# LedMatrixController.net
KiCad netlist of a schematic drawn in EAGLE
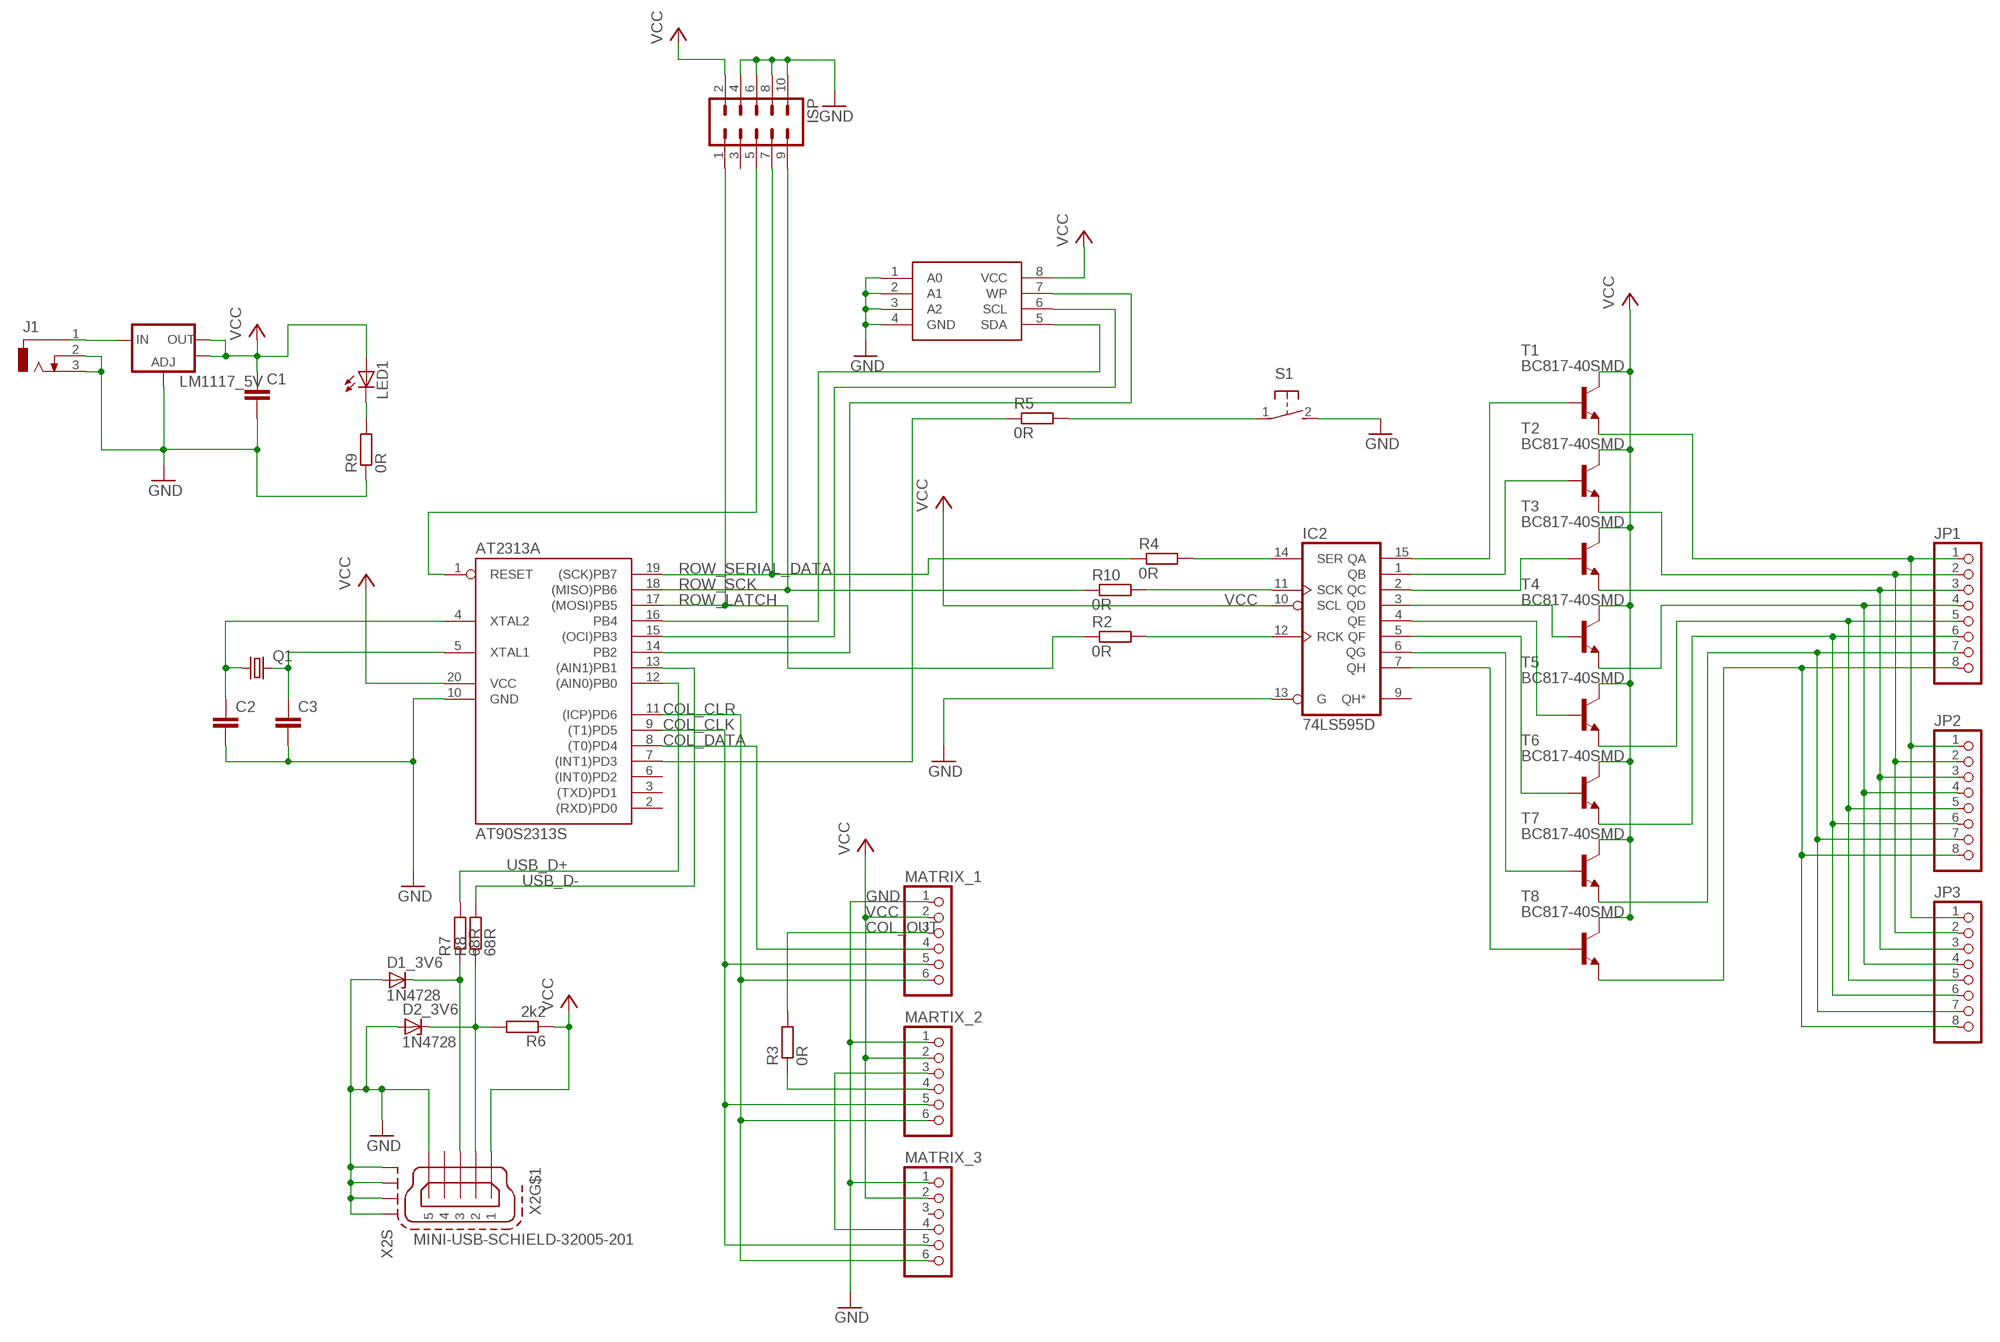
[diagram p0: schematic, sheet 1]

(export (version "E")
  (design (tool "Eeschema 10.0.6"))
  (components
    (comp (ref "AT2313A")
      (value "AT90S2313S")
      (footprint "eagle-import:SO20L")
      (libsource (lib "eagle-import") (part "AT90S2313S"))
    )
    (comp (ref "C1")
      (value "C-EU025-025X050")
      (footprint "eagle-import:C025-025X050")
      (libsource (lib "eagle-import") (part "C-EU025-025X050"))
    )
    (comp (ref "C2")
      (value "C-EUC1206")
      (footprint "eagle-import:C1206")
      (libsource (lib "eagle-import") (part "C-EUC1206"))
    )
    (comp (ref "C3")
      (value "C-EUC1206")
      (footprint "eagle-import:C1206")
      (libsource (lib "eagle-import") (part "C-EUC1206"))
    )
    (comp (ref "D1_3V6")
      (value "1N4728")
      (footprint "eagle-import:DO41Z10")
      (libsource (lib "eagle-import") (part "1N4728"))
    )
    (comp (ref "D2_3V6")
      (value "1N4728")
      (footprint "eagle-import:DO41Z10")
      (libsource (lib "eagle-import") (part "1N4728"))
    )
    (comp (ref "EEPROM")
      (value "AT24C08")
      (footprint "eagle-import:SO08")
      (libsource (lib "eagle-import") (part "AT24C08"))
    )
    (comp (ref "IC2")
      (value "74LS595D")
      (footprint "eagle-import:SO16")
      (libsource (lib "eagle-import") (part "74595DLS"))
    )
    (comp (ref "ISP")
      (value "ML10")
      (footprint "eagle-import:ML10")
      (libsource (lib "eagle-import") (part "ML10"))
    )
    (comp (ref "J1")
      (value "DCJ0303")
      (footprint "eagle-import:DCJ0303")
      (libsource (lib "eagle-import") (part "DCJ0303"))
    )
    (comp (ref "JP1")
      (value "PINHD-1X8")
      (footprint "eagle-import:1X08")
      (libsource (lib "eagle-import") (part "PINHD-1X8"))
    )
    (comp (ref "JP2")
      (value "PINHD-1X8")
      (footprint "eagle-import:1X08")
      (libsource (lib "eagle-import") (part "PINHD-1X8"))
    )
    (comp (ref "JP3")
      (value "PINHD-1X8")
      (footprint "eagle-import:1X08")
      (libsource (lib "eagle-import") (part "PINHD-1X8"))
    )
    (comp (ref "LED1")
      (value "LEDCHIPLED_1206")
      (footprint "eagle-import:CHIPLED_1206")
      (libsource (lib "eagle-import") (part "LEDCHIPLED_1206"))
    )
    (comp (ref "LM1117_5V")
      (value "V_REG_LM1117SOT223")
      (footprint "eagle-import:SOT223")
      (libsource (lib "eagle-import") (part "V_REG_LM1117SOT223"))
    )
    (comp (ref "MARTIX_2")
      (value "PINHD-1X6")
      (footprint "eagle-import:1X06")
      (libsource (lib "eagle-import") (part "PINHD-1X6"))
    )
    (comp (ref "MATRIX_1")
      (value "PINHD-1X6")
      (footprint "eagle-import:1X06")
      (libsource (lib "eagle-import") (part "PINHD-1X6"))
    )
    (comp (ref "MATRIX_3")
      (value "PINHD-1X6")
      (footprint "eagle-import:1X06")
      (libsource (lib "eagle-import") (part "PINHD-1X6"))
    )
    (comp (ref "Q1")
      (value "CRYSTALHC49UP")
      (footprint "eagle-import:HC49UP")
      (libsource (lib "eagle-import") (part "CRYSTALHC49UP"))
    )
    (comp (ref "R2")
      (value "0R")
      (footprint "eagle-import:R1206")
      (libsource (lib "eagle-import") (part "R-EU_R1206"))
    )
    (comp (ref "R3")
      (value "0R")
      (footprint "eagle-import:R1206")
      (libsource (lib "eagle-import") (part "R-EU_R1206"))
    )
    (comp (ref "R4")
      (value "0R")
      (footprint "eagle-import:R1206")
      (libsource (lib "eagle-import") (part "R-EU_R1206"))
    )
    (comp (ref "R5")
      (value "0R")
      (footprint "eagle-import:R1206")
      (libsource (lib "eagle-import") (part "R-EU_R1206"))
    )
    (comp (ref "R6")
      (value "2k2")
      (footprint "eagle-import:R1206")
      (libsource (lib "eagle-import") (part "R-EU_R1206"))
    )
    (comp (ref "R7")
      (value "68R")
      (footprint "eagle-import:R1206")
      (libsource (lib "eagle-import") (part "R-EU_R1206"))
    )
    (comp (ref "R8")
      (value "68R")
      (footprint "eagle-import:R1206")
      (libsource (lib "eagle-import") (part "R-EU_R1206"))
    )
    (comp (ref "R9")
      (value "0R")
      (footprint "eagle-import:R1206")
      (libsource (lib "eagle-import") (part "R-EU_R1206"))
    )
    (comp (ref "R10")
      (value "0R")
      (footprint "eagle-import:R1206")
      (libsource (lib "eagle-import") (part "R-EU_R1206"))
    )
    (comp (ref "S1")
      (value "31-XX")
      (footprint "eagle-import:B3F-31XX")
      (fields (field (name "MPN") "B3F-3100"))
      (libsource (lib "eagle-import") (part "31-XX"))
    )
    (comp (ref "T1")
      (value "BC817-40SMD")
      (footprint "eagle-import:SOT23-BEC")
      (libsource (lib "eagle-import") (part "BC817SMD-40"))
    )
    (comp (ref "T2")
      (value "BC817-40SMD")
      (footprint "eagle-import:SOT23-BEC")
      (libsource (lib "eagle-import") (part "BC817SMD-40"))
    )
    (comp (ref "T3")
      (value "BC817-40SMD")
      (footprint "eagle-import:SOT23-BEC")
      (libsource (lib "eagle-import") (part "BC817SMD-40"))
    )
    (comp (ref "T4")
      (value "BC817-40SMD")
      (footprint "eagle-import:SOT23-BEC")
      (libsource (lib "eagle-import") (part "BC817SMD-40"))
    )
    (comp (ref "T5")
      (value "BC817-40SMD")
      (footprint "eagle-import:SOT23-BEC")
      (libsource (lib "eagle-import") (part "BC817SMD-40"))
    )
    (comp (ref "T6")
      (value "BC817-40SMD")
      (footprint "eagle-import:SOT23-BEC")
      (libsource (lib "eagle-import") (part "BC817SMD-40"))
    )
    (comp (ref "T7")
      (value "BC817-40SMD")
      (footprint "eagle-import:SOT23-BEC")
      (libsource (lib "eagle-import") (part "BC817SMD-40"))
    )
    (comp (ref "T8")
      (value "BC817-40SMD")
      (footprint "eagle-import:SOT23-BEC")
      (libsource (lib "eagle-import") (part "BC817SMD-40"))
    )
    (comp (ref "X2")
      (value "MINI-USB-SCHIELD-32005-201")
      (footprint "eagle-import:32005-201")
      (libsource (lib "eagle-import") (part "MINI-USB-SCHIELD-32005-201"))
    )
  )
  (nets
    (net (code "1") (name "/COL_CLK") (class "Default")
      (node (ref "AT2313A") (pin "9") (pinfunction "(T1)PD5_9") (pintype "bidirectional"))
      (node (ref "MARTIX_2") (pin "5") (pinfunction "5_5") (pintype "passive"))
      (node (ref "MATRIX_1") (pin "5") (pinfunction "5_5") (pintype "passive"))
      (node (ref "MATRIX_3") (pin "5") (pinfunction "5_5") (pintype "passive"))
    )
    (net (code "2") (name "/COL_CLR") (class "Default")
      (node (ref "AT2313A") (pin "11") (pinfunction "(ICP)PD6_11") (pintype "bidirectional"))
      (node (ref "MARTIX_2") (pin "6") (pinfunction "6_6") (pintype "passive"))
      (node (ref "MATRIX_1") (pin "6") (pinfunction "6_6") (pintype "passive"))
      (node (ref "MATRIX_3") (pin "6") (pinfunction "6_6") (pintype "passive"))
    )
    (net (code "3") (name "/COL_DATA") (class "Default")
      (node (ref "AT2313A") (pin "8") (pinfunction "(T0)PD4_8") (pintype "bidirectional"))
      (node (ref "MATRIX_1") (pin "4") (pinfunction "4_4") (pintype "passive"))
    )
    (net (code "4") (name "/COL_OUT") (class "Default")
      (node (ref "MATRIX_1") (pin "3") (pinfunction "3_3") (pintype "passive"))
      (node (ref "R3") (pin "2") (pinfunction "2_2") (pintype "passive"))
    )
    (net (code "5") (name "/ROW_LATCH") (class "Default")
      (node (ref "AT2313A") (pin "17") (pinfunction "(MOSI)PB5_17") (pintype "bidirectional"))
      (node (ref "ISP") (pin "1") (pinfunction "1_1") (pintype "passive"))
      (node (ref "R2") (pin "1") (pinfunction "1_1") (pintype "passive"))
    )
    (net (code "6") (name "/ROW_SCK") (class "Default")
      (node (ref "AT2313A") (pin "18") (pinfunction "(MISO)PB6_18") (pintype "bidirectional"))
      (node (ref "ISP") (pin "9") (pinfunction "9_9") (pintype "passive"))
      (node (ref "R10") (pin "1") (pinfunction "1_1") (pintype "passive"))
    )
    (net (code "7") (name "/ROW_SERIAL_DATA") (class "Default")
      (node (ref "AT2313A") (pin "19") (pinfunction "(SCK)PB7_19") (pintype "bidirectional"))
      (node (ref "ISP") (pin "7") (pinfunction "7_7") (pintype "passive"))
      (node (ref "R4") (pin "1") (pinfunction "1_1") (pintype "passive"))
    )
    (net (code "8") (name "/USB_D+") (class "Default")
      (node (ref "AT2313A") (pin "12") (pinfunction "(AIN0)PB0_12") (pintype "bidirectional"))
      (node (ref "R7") (pin "2") (pinfunction "2_2") (pintype "passive"))
    )
    (net (code "9") (name "/USB_D-") (class "Default")
      (node (ref "AT2313A") (pin "13") (pinfunction "(AIN1)PB1_13") (pintype "bidirectional"))
      (node (ref "R8") (pin "2") (pinfunction "2_2") (pintype "passive"))
    )
    (net (code "10") (name "GND") (class "Default")
      (node (ref "AT2313A") (pin "10") (pinfunction "GND_10") (pintype "power_in"))
      (node (ref "C1") (pin "2") (pinfunction "2_2") (pintype "passive"))
      (node (ref "C2") (pin "2") (pinfunction "2_2") (pintype "passive"))
      (node (ref "C3") (pin "2") (pinfunction "2_2") (pintype "passive"))
      (node (ref "D1_3V6") (pin "A") (pinfunction "A_A") (pintype "passive"))
      (node (ref "D2_3V6") (pin "A") (pinfunction "A_A") (pintype "passive"))
      (node (ref "EEPROM") (pin "1") (pinfunction "A0_1") (pintype "bidirectional"))
      (node (ref "EEPROM") (pin "2") (pinfunction "A1_2") (pintype "bidirectional"))
      (node (ref "EEPROM") (pin "3") (pinfunction "A2_3") (pintype "bidirectional"))
      (node (ref "EEPROM") (pin "4") (pinfunction "GND_4") (pintype "bidirectional"))
      (node (ref "IC2") (pin "13") (pinfunction "G_13") (pintype "input"))
      (node (ref "ISP") (pin "10") (pinfunction "10_10") (pintype "passive"))
      (node (ref "ISP") (pin "4") (pinfunction "4_4") (pintype "passive"))
      (node (ref "ISP") (pin "6") (pinfunction "6_6") (pintype "passive"))
      (node (ref "ISP") (pin "8") (pinfunction "8_8") (pintype "passive"))
      (node (ref "J1") (pin "2") (pinfunction "2_2") (pintype "passive"))
      (node (ref "J1") (pin "3") (pinfunction "3_3") (pintype "passive"))
      (node (ref "LM1117_5V") (pin "1") (pinfunction "ADJ_1") (pintype "input"))
      (node (ref "MARTIX_2") (pin "1") (pinfunction "1_1") (pintype "passive"))
      (node (ref "MATRIX_1") (pin "1") (pinfunction "1_1") (pintype "passive"))
      (node (ref "MATRIX_3") (pin "1") (pinfunction "1_1") (pintype "passive"))
      (node (ref "R9") (pin "1") (pinfunction "1_1") (pintype "passive"))
      (node (ref "S1") (pin "2") (pinfunction "S_2") (pintype "passive"))
      (node (ref "X2") (pin "5") (pinfunction "5_5") (pintype "passive"))
      (node (ref "X2") (pin "M1") (pinfunction "S1_M1") (pintype "passive"))
      (node (ref "X2") (pin "M2") (pinfunction "S2_M2") (pintype "passive"))
      (node (ref "X2") (pin "M3") (pinfunction "S3_M3") (pintype "passive"))
      (node (ref "X2") (pin "M4") (pinfunction "S4_M4") (pintype "passive"))
    )
    (net (code "11") (name "Net-(AT2313A-(INT1)PD3)") (class "Default")
      (node (ref "AT2313A") (pin "7") (pinfunction "(INT1)PD3_7") (pintype "bidirectional"))
      (node (ref "R5") (pin "1") (pinfunction "1_1") (pintype "passive"))
    )
    (net (code "12") (name "Net-(AT2313A-(OCI)PB3)") (class "Default")
      (node (ref "AT2313A") (pin "15") (pinfunction "(OCI)PB3_15") (pintype "bidirectional"))
      (node (ref "EEPROM") (pin "6") (pinfunction "SCL_6") (pintype "bidirectional"))
    )
    (net (code "13") (name "Net-(AT2313A-PB2)") (class "Default")
      (node (ref "AT2313A") (pin "14") (pinfunction "PB2_14") (pintype "bidirectional"))
      (node (ref "EEPROM") (pin "7") (pinfunction "WP_7") (pintype "bidirectional"))
    )
    (net (code "14") (name "Net-(AT2313A-PB4)") (class "Default")
      (node (ref "AT2313A") (pin "16") (pinfunction "PB4_16") (pintype "bidirectional"))
      (node (ref "EEPROM") (pin "5") (pinfunction "SDA_5") (pintype "bidirectional"))
    )
    (net (code "15") (name "Net-(AT2313A-RESET)") (class "Default")
      (node (ref "AT2313A") (pin "1") (pinfunction "RESET_1") (pintype "bidirectional"))
      (node (ref "ISP") (pin "5") (pinfunction "5_5") (pintype "passive"))
    )
    (net (code "16") (name "Net-(AT2313A-XTAL1)") (class "Default")
      (node (ref "AT2313A") (pin "5") (pinfunction "XTAL1_5") (pintype "bidirectional"))
      (node (ref "C3") (pin "1") (pinfunction "1_1") (pintype "passive"))
      (node (ref "Q1") (pin "2") (pinfunction "2_2") (pintype "passive"))
    )
    (net (code "17") (name "Net-(AT2313A-XTAL2)") (class "Default")
      (node (ref "AT2313A") (pin "4") (pinfunction "XTAL2_4") (pintype "bidirectional"))
      (node (ref "C2") (pin "1") (pinfunction "1_1") (pintype "passive"))
      (node (ref "Q1") (pin "1") (pinfunction "1_1") (pintype "passive"))
    )
    (net (code "18") (name "Net-(D1_3V6-PadC)") (class "Default")
      (node (ref "D1_3V6") (pin "C") (pinfunction "C_C") (pintype "passive"))
      (node (ref "R7") (pin "1") (pinfunction "1_1") (pintype "passive"))
      (node (ref "X2") (pin "3") (pinfunction "3_3") (pintype "passive"))
    )
    (net (code "19") (name "Net-(D2_3V6-PadC)") (class "Default")
      (node (ref "D2_3V6") (pin "C") (pinfunction "C_C") (pintype "passive"))
      (node (ref "R6") (pin "2") (pinfunction "2_2") (pintype "passive"))
      (node (ref "R8") (pin "1") (pinfunction "1_1") (pintype "passive"))
      (node (ref "X2") (pin "2") (pinfunction "2_2") (pintype "passive"))
    )
    (net (code "20") (name "Net-(IC2A-QA)") (class "Default")
      (node (ref "IC2") (pin "15") (pinfunction "QA_15") (pintype "tri_state"))
      (node (ref "T1") (pin "B") (pinfunction "B_B") (pintype "passive"))
    )
    (net (code "21") (name "Net-(IC2A-QB)") (class "Default")
      (node (ref "IC2") (pin "1") (pinfunction "QB_1") (pintype "tri_state"))
      (node (ref "T2") (pin "B") (pinfunction "B_B") (pintype "passive"))
    )
    (net (code "22") (name "Net-(IC2A-QC)") (class "Default")
      (node (ref "IC2") (pin "2") (pinfunction "QC_2") (pintype "tri_state"))
      (node (ref "T3") (pin "B") (pinfunction "B_B") (pintype "passive"))
    )
    (net (code "23") (name "Net-(IC2A-QD)") (class "Default")
      (node (ref "IC2") (pin "3") (pinfunction "QD_3") (pintype "tri_state"))
      (node (ref "T4") (pin "B") (pinfunction "B_B") (pintype "passive"))
    )
    (net (code "24") (name "Net-(IC2A-QE)") (class "Default")
      (node (ref "IC2") (pin "4") (pinfunction "QE_4") (pintype "tri_state"))
      (node (ref "T5") (pin "B") (pinfunction "B_B") (pintype "passive"))
    )
    (net (code "25") (name "Net-(IC2A-QF)") (class "Default")
      (node (ref "IC2") (pin "5") (pinfunction "QF_5") (pintype "tri_state"))
      (node (ref "T6") (pin "B") (pinfunction "B_B") (pintype "passive"))
    )
    (net (code "26") (name "Net-(IC2A-QG)") (class "Default")
      (node (ref "IC2") (pin "6") (pinfunction "QG_6") (pintype "tri_state"))
      (node (ref "T7") (pin "B") (pinfunction "B_B") (pintype "passive"))
    )
    (net (code "27") (name "Net-(IC2A-QH)") (class "Default")
      (node (ref "IC2") (pin "7") (pinfunction "QH_7") (pintype "tri_state"))
      (node (ref "T8") (pin "B") (pinfunction "B_B") (pintype "passive"))
    )
    (net (code "28") (name "Net-(IC2A-RCK)") (class "Default")
      (node (ref "IC2") (pin "12") (pinfunction "RCK_12") (pintype "input"))
      (node (ref "R2") (pin "2") (pinfunction "2_2") (pintype "passive"))
    )
    (net (code "29") (name "Net-(IC2A-SCK)") (class "Default")
      (node (ref "IC2") (pin "11") (pinfunction "SCK_11") (pintype "input"))
      (node (ref "R10") (pin "2") (pinfunction "2_2") (pintype "passive"))
    )
    (net (code "30") (name "Net-(IC2A-SER)") (class "Default")
      (node (ref "IC2") (pin "14") (pinfunction "SER_14") (pintype "input"))
      (node (ref "R4") (pin "2") (pinfunction "2_2") (pintype "passive"))
    )
    (net (code "31") (name "Net-(JP1-Pad1)") (class "Default")
      (node (ref "JP1") (pin "1") (pinfunction "1_1") (pintype "passive"))
      (node (ref "JP2") (pin "1") (pinfunction "1_1") (pintype "passive"))
      (node (ref "JP3") (pin "1") (pinfunction "1_1") (pintype "passive"))
      (node (ref "T1") (pin "E") (pinfunction "E_E") (pintype "passive"))
    )
    (net (code "32") (name "Net-(JP1-Pad2)") (class "Default")
      (node (ref "JP1") (pin "2") (pinfunction "2_2") (pintype "passive"))
      (node (ref "JP2") (pin "2") (pinfunction "2_2") (pintype "passive"))
      (node (ref "JP3") (pin "2") (pinfunction "2_2") (pintype "passive"))
      (node (ref "T2") (pin "E") (pinfunction "E_E") (pintype "passive"))
    )
    (net (code "33") (name "Net-(JP1-Pad3)") (class "Default")
      (node (ref "JP1") (pin "3") (pinfunction "3_3") (pintype "passive"))
      (node (ref "JP2") (pin "3") (pinfunction "3_3") (pintype "passive"))
      (node (ref "JP3") (pin "3") (pinfunction "3_3") (pintype "passive"))
      (node (ref "T3") (pin "E") (pinfunction "E_E") (pintype "passive"))
    )
    (net (code "34") (name "Net-(JP1-Pad4)") (class "Default")
      (node (ref "JP1") (pin "4") (pinfunction "4_4") (pintype "passive"))
      (node (ref "JP2") (pin "4") (pinfunction "4_4") (pintype "passive"))
      (node (ref "JP3") (pin "4") (pinfunction "4_4") (pintype "passive"))
      (node (ref "T4") (pin "E") (pinfunction "E_E") (pintype "passive"))
    )
    (net (code "35") (name "Net-(JP1-Pad5)") (class "Default")
      (node (ref "JP1") (pin "5") (pinfunction "5_5") (pintype "passive"))
      (node (ref "JP2") (pin "5") (pinfunction "5_5") (pintype "passive"))
      (node (ref "JP3") (pin "5") (pinfunction "5_5") (pintype "passive"))
      (node (ref "T5") (pin "E") (pinfunction "E_E") (pintype "passive"))
    )
    (net (code "36") (name "Net-(JP1-Pad6)") (class "Default")
      (node (ref "JP1") (pin "6") (pinfunction "6_6") (pintype "passive"))
      (node (ref "JP2") (pin "6") (pinfunction "6_6") (pintype "passive"))
      (node (ref "JP3") (pin "6") (pinfunction "6_6") (pintype "passive"))
      (node (ref "T6") (pin "E") (pinfunction "E_E") (pintype "passive"))
    )
    (net (code "37") (name "Net-(JP1-Pad7)") (class "Default")
      (node (ref "JP1") (pin "7") (pinfunction "7_7") (pintype "passive"))
      (node (ref "JP2") (pin "7") (pinfunction "7_7") (pintype "passive"))
      (node (ref "JP3") (pin "7") (pinfunction "7_7") (pintype "passive"))
      (node (ref "T7") (pin "E") (pinfunction "E_E") (pintype "passive"))
    )
    (net (code "38") (name "Net-(JP1-Pad8)") (class "Default")
      (node (ref "JP1") (pin "8") (pinfunction "8_8") (pintype "passive"))
      (node (ref "JP2") (pin "8") (pinfunction "8_8") (pintype "passive"))
      (node (ref "JP3") (pin "8") (pinfunction "8_8") (pintype "passive"))
      (node (ref "T8") (pin "E") (pinfunction "E_E") (pintype "passive"))
    )
    (net (code "39") (name "Net-(LED1-PadC)") (class "Default")
      (node (ref "LED1") (pin "C") (pinfunction "C_C") (pintype "passive"))
      (node (ref "R9") (pin "2") (pinfunction "2_2") (pintype "passive"))
    )
    (net (code "40") (name "Net-(LM1117_5V-IN)") (class "Default")
      (node (ref "J1") (pin "1") (pinfunction "1_1") (pintype "passive"))
      (node (ref "LM1117_5V") (pin "3") (pinfunction "IN_3") (pintype "input"))
    )
    (net (code "41") (name "Net-(MARTIX_2-Pad3)") (class "Default")
      (node (ref "MARTIX_2") (pin "3") (pinfunction "3_3") (pintype "passive"))
      (node (ref "MATRIX_3") (pin "4") (pinfunction "4_4") (pintype "passive"))
    )
    (net (code "42") (name "Net-(MARTIX_2-Pad4)") (class "Default")
      (node (ref "MARTIX_2") (pin "4") (pinfunction "4_4") (pintype "passive"))
      (node (ref "R3") (pin "1") (pinfunction "1_1") (pintype "passive"))
    )
    (net (code "43") (name "Net-(S1-P)") (class "Default")
      (node (ref "R5") (pin "2") (pinfunction "2_2") (pintype "passive"))
      (node (ref "S1") (pin "1") (pinfunction "P_1") (pintype "passive"))
    )
    (net (code "44") (name "VCC") (class "Default")
      (node (ref "AT2313A") (pin "20") (pinfunction "VCC_20") (pintype "power_in"))
      (node (ref "C1") (pin "1") (pinfunction "1_1") (pintype "passive"))
      (node (ref "EEPROM") (pin "8") (pinfunction "VCC_8") (pintype "bidirectional"))
      (node (ref "IC2") (pin "10") (pinfunction "SCL_10") (pintype "input"))
      (node (ref "ISP") (pin "2") (pinfunction "2_2") (pintype "passive"))
      (node (ref "LED1") (pin "A") (pinfunction "A_A") (pintype "passive"))
      (node (ref "LM1117_5V") (pin "2") (pinfunction "OUT_2") (pintype "output"))
      (node (ref "LM1117_5V") (pin "4") (pinfunction "OUT_4") (pintype "output"))
      (node (ref "MARTIX_2") (pin "2") (pinfunction "2_2") (pintype "passive"))
      (node (ref "MATRIX_1") (pin "2") (pinfunction "2_2") (pintype "passive"))
      (node (ref "MATRIX_3") (pin "2") (pinfunction "2_2") (pintype "passive"))
      (node (ref "R6") (pin "1") (pinfunction "1_1") (pintype "passive"))
      (node (ref "T1") (pin "C") (pinfunction "C_C") (pintype "passive"))
      (node (ref "T2") (pin "C") (pinfunction "C_C") (pintype "passive"))
      (node (ref "T3") (pin "C") (pinfunction "C_C") (pintype "passive"))
      (node (ref "T4") (pin "C") (pinfunction "C_C") (pintype "passive"))
      (node (ref "T5") (pin "C") (pinfunction "C_C") (pintype "passive"))
      (node (ref "T6") (pin "C") (pinfunction "C_C") (pintype "passive"))
      (node (ref "T7") (pin "C") (pinfunction "C_C") (pintype "passive"))
      (node (ref "T8") (pin "C") (pinfunction "C_C") (pintype "passive"))
      (node (ref "X2") (pin "1") (pinfunction "1_1") (pintype "passive"))
    )
    (net (code "45") (name "unconnected-(AT2313A-(INT0)PD2-Pad6)") (class "Default")
      (node (ref "AT2313A") (pin "6") (pinfunction "(INT0)PD2_6") (pintype "bidirectional"))
    )
    (net (code "46") (name "unconnected-(AT2313A-(RXD)PD0-Pad2)") (class "Default")
      (node (ref "AT2313A") (pin "2") (pinfunction "(RXD)PD0_2") (pintype "bidirectional"))
    )
    (net (code "47") (name "unconnected-(AT2313A-(TXD)PD1-Pad3)") (class "Default")
      (node (ref "AT2313A") (pin "3") (pinfunction "(TXD)PD1_3") (pintype "bidirectional"))
    )
    (net (code "48") (name "unconnected-(IC2A-QH*-Pad9)") (class "Default")
      (node (ref "IC2") (pin "9") (pinfunction "QH*_9") (pintype "tri_state"))
    )
    (net (code "49") (name "unconnected-(ISP-Pad3)") (class "Default")
      (node (ref "ISP") (pin "3") (pinfunction "3_3") (pintype "passive"))
    )
    (net (code "50") (name "unconnected-(MATRIX_3-Pad3)") (class "Default")
      (node (ref "MATRIX_3") (pin "3") (pinfunction "3_3") (pintype "passive"))
    )
    (net (code "51") (name "unconnected-(X2-Pad4)") (class "Default")
      (node (ref "X2") (pin "4") (pinfunction "4_4") (pintype "passive"))
    )
  )
)
